# amplifier_v0001_-_1_Channel_Test.net
KiCad netlist of a schematic drawn in EAGLE
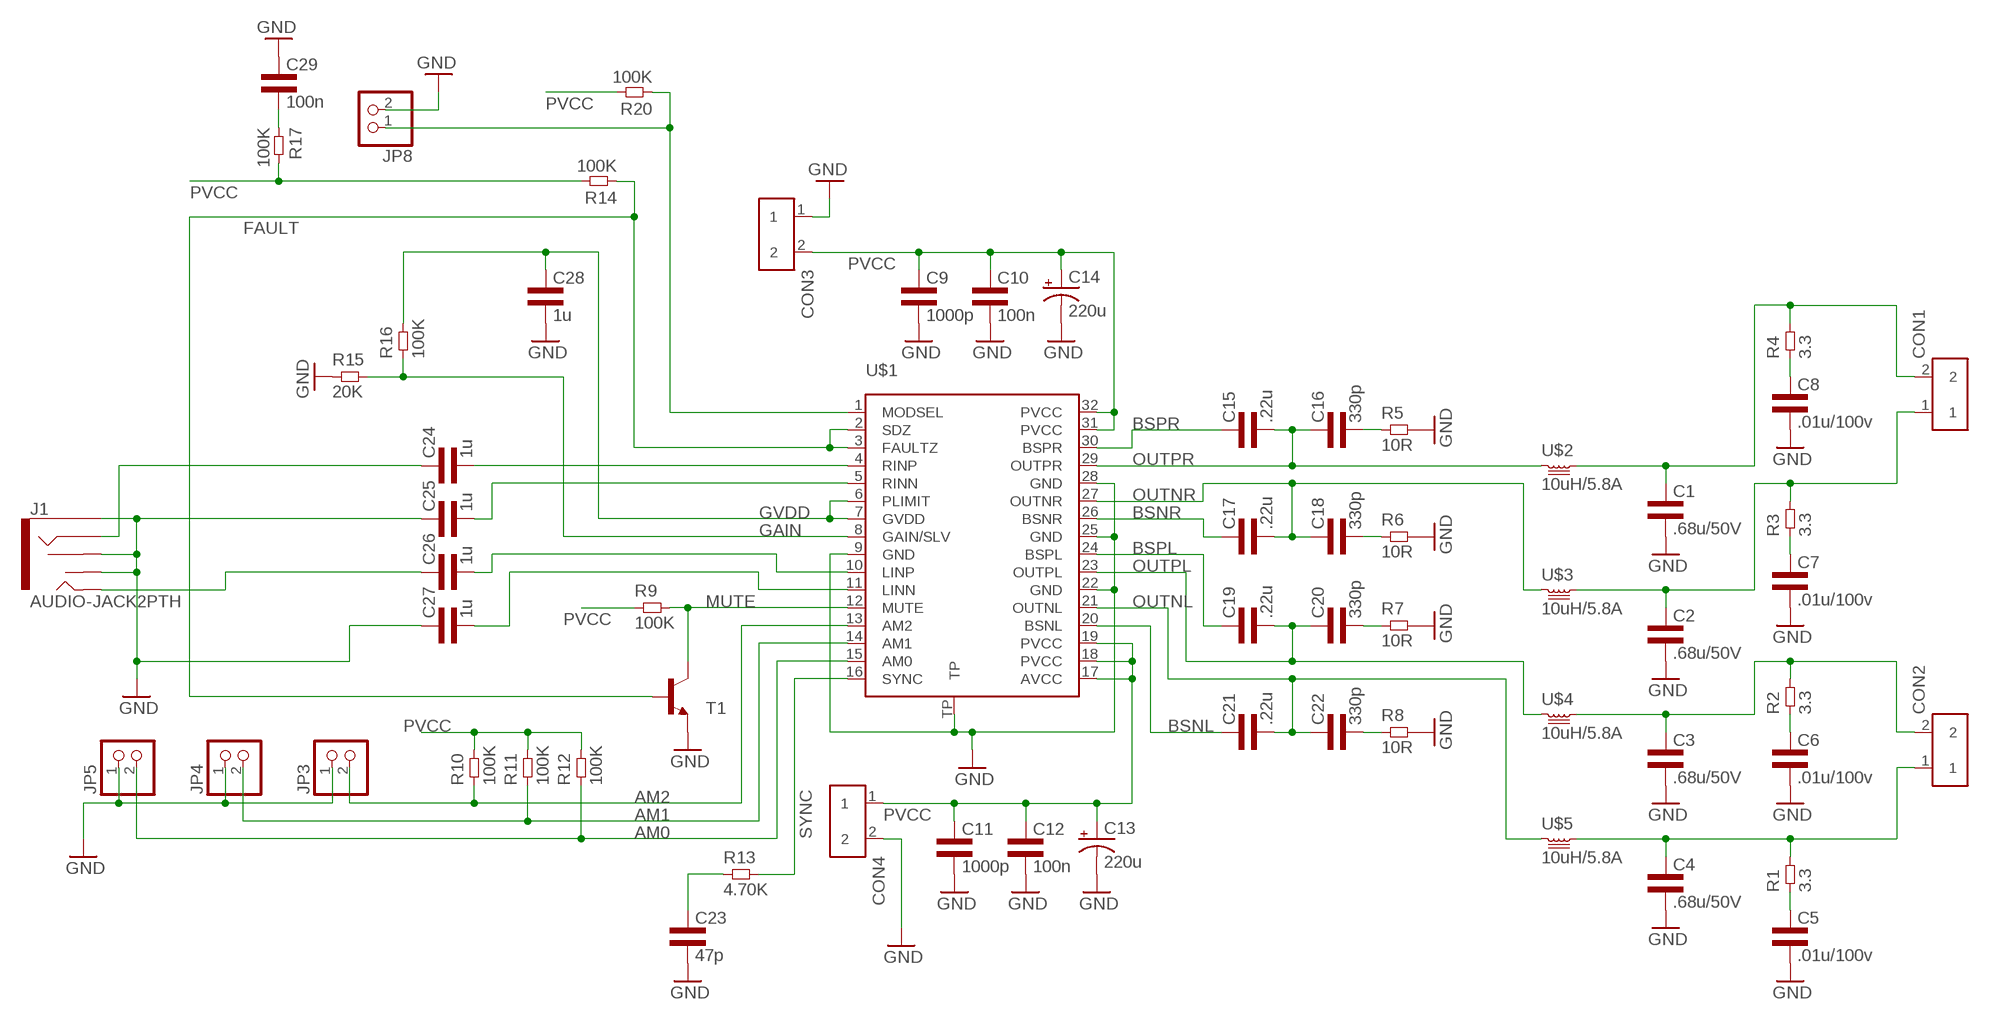
[diagram p0: schematic, sheet 1]

(export (version "E")
  (design (tool "Eeschema 10.0.6"))
  (components
    (comp (ref "C1")
      (value ".68u/50V")
      (footprint "eagle-import:1206L3")
      (libsource (lib "eagle-import") (part "CAP1206L3"))
    )
    (comp (ref "C2")
      (value ".68u/50V")
      (footprint "eagle-import:1206L3")
      (libsource (lib "eagle-import") (part "CAP1206L3"))
    )
    (comp (ref "C3")
      (value ".68u/50V")
      (footprint "eagle-import:1206L3")
      (libsource (lib "eagle-import") (part "CAP1206L3"))
    )
    (comp (ref "C4")
      (value ".68u/50V")
      (footprint "eagle-import:1206L3")
      (libsource (lib "eagle-import") (part "CAP1206L3"))
    )
    (comp (ref "C5")
      (value ".01u/100v")
      (footprint "eagle-import:0805L3")
      (libsource (lib "eagle-import") (part "CAP0805L3"))
    )
    (comp (ref "C6")
      (value ".01u/100v")
      (footprint "eagle-import:0805L3")
      (libsource (lib "eagle-import") (part "CAP0805L3"))
    )
    (comp (ref "C7")
      (value ".01u/100v")
      (footprint "eagle-import:0805L3")
      (libsource (lib "eagle-import") (part "CAP0805L3"))
    )
    (comp (ref "C8")
      (value ".01u/100v")
      (footprint "eagle-import:0805L3")
      (libsource (lib "eagle-import") (part "CAP0805L3"))
    )
    (comp (ref "C9")
      (value "1000p")
      (footprint "eagle-import:0603L3")
      (libsource (lib "eagle-import") (part "CAP0603L3"))
    )
    (comp (ref "C10")
      (value "100n")
      (footprint "eagle-import:0603L3")
      (libsource (lib "eagle-import") (part "CAP0603L3"))
    )
    (comp (ref "C11")
      (value "1000p")
      (footprint "eagle-import:0603L3")
      (libsource (lib "eagle-import") (part "CAP0603L3"))
    )
    (comp (ref "C12")
      (value "100n")
      (footprint "eagle-import:0603L3")
      (libsource (lib "eagle-import") (part "CAP0603L3"))
    )
    (comp (ref "C13")
      (value "220u")
      (footprint "eagle-import:E5-10,5")
      (libsource (lib "eagle-import") (part "CPOL-USE5-10.5"))
    )
    (comp (ref "C14")
      (value "220u")
      (footprint "eagle-import:E5-10,5")
      (libsource (lib "eagle-import") (part "CPOL-USE5-10.5"))
    )
    (comp (ref "C15")
      (value ".22u")
      (footprint "eagle-import:0603L3")
      (libsource (lib "eagle-import") (part "CAP0603L3"))
    )
    (comp (ref "C16")
      (value "330p")
      (footprint "eagle-import:0603L3")
      (libsource (lib "eagle-import") (part "CAP0603L3"))
    )
    (comp (ref "C17")
      (value ".22u")
      (footprint "eagle-import:0603L3")
      (libsource (lib "eagle-import") (part "CAP0603L3"))
    )
    (comp (ref "C18")
      (value "330p")
      (footprint "eagle-import:0603L3")
      (libsource (lib "eagle-import") (part "CAP0603L3"))
    )
    (comp (ref "C19")
      (value ".22u")
      (footprint "eagle-import:0603L3")
      (libsource (lib "eagle-import") (part "CAP0603L3"))
    )
    (comp (ref "C20")
      (value "330p")
      (footprint "eagle-import:0603L3")
      (libsource (lib "eagle-import") (part "CAP0603L3"))
    )
    (comp (ref "C21")
      (value ".22u")
      (footprint "eagle-import:0603L3")
      (libsource (lib "eagle-import") (part "CAP0603L3"))
    )
    (comp (ref "C22")
      (value "330p")
      (footprint "eagle-import:0603L3")
      (libsource (lib "eagle-import") (part "CAP0603L3"))
    )
    (comp (ref "C23")
      (value "47p")
      (footprint "eagle-import:0603L3")
      (libsource (lib "eagle-import") (part "CAP0603L3"))
    )
    (comp (ref "C24")
      (value "1u")
      (footprint "eagle-import:0603L3")
      (libsource (lib "eagle-import") (part "CAP0603L3"))
    )
    (comp (ref "C25")
      (value "1u")
      (footprint "eagle-import:0603L3")
      (libsource (lib "eagle-import") (part "CAP0603L3"))
    )
    (comp (ref "C26")
      (value "1u")
      (footprint "eagle-import:0603L3")
      (libsource (lib "eagle-import") (part "CAP0603L3"))
    )
    (comp (ref "C27")
      (value "1u")
      (footprint "eagle-import:0603L3")
      (libsource (lib "eagle-import") (part "CAP0603L3"))
    )
    (comp (ref "C28")
      (value "1u")
      (footprint "eagle-import:0603L3")
      (libsource (lib "eagle-import") (part "CAP0603L3"))
    )
    (comp (ref "C29")
      (value "100n")
      (footprint "eagle-import:0603L3")
      (libsource (lib "eagle-import") (part "CAP0603L3"))
    )
    (comp (ref "CON1")
      (value "TERM_BLOCK_2")
      (footprint "eagle-import:TERM_BLOCK_2")
      (libsource (lib "eagle-import") (part "TERM_BLOCK_2"))
    )
    (comp (ref "CON2")
      (value "TERM_BLOCK_2")
      (footprint "eagle-import:TERM_BLOCK_2")
      (libsource (lib "eagle-import") (part "TERM_BLOCK_2"))
    )
    (comp (ref "CON3")
      (value "TERM_BLOCK_2")
      (footprint "eagle-import:TERM_BLOCK_2")
      (libsource (lib "eagle-import") (part "TERM_BLOCK_2"))
    )
    (comp (ref "CON4")
      (value "TERM_BLOCK_2")
      (footprint "eagle-import:TERM_BLOCK_2")
      (libsource (lib "eagle-import") (part "TERM_BLOCK_2"))
    )
    (comp (ref "J1")
      (value "AUDIO-JACK2PTH")
      (footprint "eagle-import:AUDIO-JACK")
      (libsource (lib "eagle-import") (part "AUDIO-JACK2PTH"))
    )
    (comp (ref "JP3")
      (value "PINHD-1X2")
      (footprint "eagle-import:1X02")
      (libsource (lib "eagle-import") (part "PINHD-1X2"))
    )
    (comp (ref "JP4")
      (value "PINHD-1X2")
      (footprint "eagle-import:1X02")
      (libsource (lib "eagle-import") (part "PINHD-1X2"))
    )
    (comp (ref "JP5")
      (value "PINHD-1X2")
      (footprint "eagle-import:1X02")
      (libsource (lib "eagle-import") (part "PINHD-1X2"))
    )
    (comp (ref "JP8")
      (value "PINHD-1X2")
      (footprint "eagle-import:1X02")
      (libsource (lib "eagle-import") (part "PINHD-1X2"))
    )
    (comp (ref "R1")
      (value "3.3")
      (footprint "eagle-import:0603L3")
      (libsource (lib "eagle-import") (part "RES0603L3"))
    )
    (comp (ref "R2")
      (value "3.3")
      (footprint "eagle-import:0603L3")
      (libsource (lib "eagle-import") (part "RES0603L3"))
    )
    (comp (ref "R3")
      (value "3.3")
      (footprint "eagle-import:0603L3")
      (libsource (lib "eagle-import") (part "RES0603L3"))
    )
    (comp (ref "R4")
      (value "3.3")
      (footprint "eagle-import:0603L3")
      (libsource (lib "eagle-import") (part "RES0603L3"))
    )
    (comp (ref "R5")
      (value "10R")
      (footprint "eagle-import:0805L3")
      (libsource (lib "eagle-import") (part "RES0805L3"))
    )
    (comp (ref "R6")
      (value "10R")
      (footprint "eagle-import:0805L3")
      (libsource (lib "eagle-import") (part "RES0805L3"))
    )
    (comp (ref "R7")
      (value "10R")
      (footprint "eagle-import:0805L3")
      (libsource (lib "eagle-import") (part "RES0805L3"))
    )
    (comp (ref "R8")
      (value "10R")
      (footprint "eagle-import:0805L3")
      (libsource (lib "eagle-import") (part "RES0805L3"))
    )
    (comp (ref "R9")
      (value "100K")
      (footprint "eagle-import:0603L3")
      (libsource (lib "eagle-import") (part "RES0603L3"))
    )
    (comp (ref "R10")
      (value "100K")
      (footprint "eagle-import:0603L3")
      (libsource (lib "eagle-import") (part "RES0603L3"))
    )
    (comp (ref "R11")
      (value "100K")
      (footprint "eagle-import:0603L3")
      (libsource (lib "eagle-import") (part "RES0603L3"))
    )
    (comp (ref "R12")
      (value "100K")
      (footprint "eagle-import:0603L3")
      (libsource (lib "eagle-import") (part "RES0603L3"))
    )
    (comp (ref "R13")
      (value "4.70K")
      (footprint "eagle-import:0603L3")
      (libsource (lib "eagle-import") (part "RES0603L3"))
    )
    (comp (ref "R14")
      (value "100K")
      (footprint "eagle-import:0603L3")
      (libsource (lib "eagle-import") (part "RES0603L3"))
    )
    (comp (ref "R15")
      (value "20K")
      (footprint "eagle-import:0603L3")
      (libsource (lib "eagle-import") (part "RES0603L3"))
    )
    (comp (ref "R16")
      (value "100K")
      (footprint "eagle-import:0603L3")
      (libsource (lib "eagle-import") (part "RES0603L3"))
    )
    (comp (ref "R17")
      (value "100K")
      (footprint "eagle-import:0603L3")
      (libsource (lib "eagle-import") (part "RES0603L3"))
    )
    (comp (ref "R20")
      (value "100K")
      (footprint "eagle-import:0603L3")
      (libsource (lib "eagle-import") (part "RES0603L3"))
    )
    (comp (ref "T1")
      (value "TRANSISTOR_MMBT2222ALT1-NPN-SOT23-BEC")
      (footprint "eagle-import:TRANSISTOR_SOT23-BEC")
      (libsource (lib "eagle-import") (part "TRANSISTOR_-NPN-SOT23-BECMMBT2222ALT1"))
    )
    (comp (ref "U$1")
      (value "TPA3116")
      (footprint "eagle-import:R-PDSO-32")
      (libsource (lib "eagle-import") (part "TPA3116"))
    )
    (comp (ref "U$2")
      (value "10uH/5.8A")
      (footprint "eagle-import:DR127")
      (libsource (lib "eagle-import") (part "INDUCTORDR127"))
    )
    (comp (ref "U$3")
      (value "10uH/5.8A")
      (footprint "eagle-import:DR127")
      (libsource (lib "eagle-import") (part "INDUCTORDR127"))
    )
    (comp (ref "U$4")
      (value "10uH/5.8A")
      (footprint "eagle-import:DR127")
      (libsource (lib "eagle-import") (part "INDUCTORDR127"))
    )
    (comp (ref "U$5")
      (value "10uH/5.8A")
      (footprint "eagle-import:DR127")
      (libsource (lib "eagle-import") (part "INDUCTORDR127"))
    )
  )
  (nets
    (net (code "1") (name "/AM0") (class "Default")
      (node (ref "JP5") (pin "2") (pinfunction "2_2") (pintype "passive"))
      (node (ref "R12") (pin "P$1") (pinfunction "1_P$1") (pintype "bidirectional"))
      (node (ref "U$1") (pin "15") (pinfunction "AM0_15") (pintype "bidirectional"))
    )
    (net (code "2") (name "/AM1") (class "Default")
      (node (ref "JP4") (pin "2") (pinfunction "2_2") (pintype "passive"))
      (node (ref "R11") (pin "P$1") (pinfunction "1_P$1") (pintype "bidirectional"))
      (node (ref "U$1") (pin "14") (pinfunction "AM1_14") (pintype "bidirectional"))
    )
    (net (code "3") (name "/AM2") (class "Default")
      (node (ref "JP3") (pin "2") (pinfunction "2_2") (pintype "passive"))
      (node (ref "R10") (pin "P$1") (pinfunction "1_P$1") (pintype "bidirectional"))
      (node (ref "U$1") (pin "13") (pinfunction "AM2_13") (pintype "bidirectional"))
    )
    (net (code "4") (name "/BSNL") (class "Default")
      (node (ref "C21") (pin "P$1") (pinfunction "1_P$1") (pintype "bidirectional"))
      (node (ref "U$1") (pin "20") (pinfunction "BSNL_20") (pintype "bidirectional"))
    )
    (net (code "5") (name "/BSNR") (class "Default")
      (node (ref "C17") (pin "P$1") (pinfunction "1_P$1") (pintype "bidirectional"))
      (node (ref "U$1") (pin "26") (pinfunction "BSNR_26") (pintype "bidirectional"))
    )
    (net (code "6") (name "/BSPL") (class "Default")
      (node (ref "C19") (pin "P$1") (pinfunction "1_P$1") (pintype "bidirectional"))
      (node (ref "U$1") (pin "24") (pinfunction "BSPL_24") (pintype "bidirectional"))
    )
    (net (code "7") (name "/BSPR") (class "Default")
      (node (ref "C15") (pin "P$1") (pinfunction "1_P$1") (pintype "bidirectional"))
      (node (ref "U$1") (pin "30") (pinfunction "BSPR_30") (pintype "bidirectional"))
    )
    (net (code "8") (name "/FAULT") (class "Default")
      (node (ref "R14") (pin "P$1") (pinfunction "1_P$1") (pintype "bidirectional"))
      (node (ref "T1") (pin "B") (pinfunction "B_B") (pintype "passive"))
      (node (ref "U$1") (pin "2") (pinfunction "SDZ_2") (pintype "bidirectional"))
      (node (ref "U$1") (pin "3") (pinfunction "FAULTZ_3") (pintype "bidirectional"))
    )
    (net (code "9") (name "/GAIN") (class "Default")
      (node (ref "R15") (pin "P$2") (pinfunction "2_P$2") (pintype "bidirectional"))
      (node (ref "R16") (pin "P$1") (pinfunction "1_P$1") (pintype "bidirectional"))
      (node (ref "U$1") (pin "8") (pinfunction "GAIN/SLV_8") (pintype "bidirectional"))
    )
    (net (code "10") (name "/GVDD") (class "Default")
      (node (ref "C28") (pin "P$1") (pinfunction "1_P$1") (pintype "bidirectional"))
      (node (ref "R16") (pin "P$2") (pinfunction "2_P$2") (pintype "bidirectional"))
      (node (ref "U$1") (pin "6") (pinfunction "PLIMIT_6") (pintype "bidirectional"))
      (node (ref "U$1") (pin "7") (pinfunction "GVDD_7") (pintype "bidirectional"))
    )
    (net (code "11") (name "/MUTE") (class "Default")
      (node (ref "R9") (pin "P$2") (pinfunction "2_P$2") (pintype "bidirectional"))
      (node (ref "T1") (pin "C") (pinfunction "C_C") (pintype "passive"))
      (node (ref "U$1") (pin "12") (pinfunction "MUTE_12") (pintype "bidirectional"))
    )
    (net (code "12") (name "/OUTNL") (class "Default")
      (node (ref "C21") (pin "P$2") (pinfunction "2_P$2") (pintype "bidirectional"))
      (node (ref "C22") (pin "P$1") (pinfunction "1_P$1") (pintype "bidirectional"))
      (node (ref "U$1") (pin "21") (pinfunction "OUTNL_21") (pintype "bidirectional"))
      (node (ref "U$5") (pin "1") (pinfunction "1_1") (pintype "bidirectional"))
    )
    (net (code "13") (name "/OUTNR") (class "Default")
      (node (ref "C17") (pin "P$2") (pinfunction "2_P$2") (pintype "bidirectional"))
      (node (ref "C18") (pin "P$1") (pinfunction "1_P$1") (pintype "bidirectional"))
      (node (ref "U$1") (pin "27") (pinfunction "OUTNR_27") (pintype "bidirectional"))
      (node (ref "U$3") (pin "1") (pinfunction "1_1") (pintype "bidirectional"))
    )
    (net (code "14") (name "/OUTPL") (class "Default")
      (node (ref "C19") (pin "P$2") (pinfunction "2_P$2") (pintype "bidirectional"))
      (node (ref "C20") (pin "P$1") (pinfunction "1_P$1") (pintype "bidirectional"))
      (node (ref "U$1") (pin "23") (pinfunction "OUTPL_23") (pintype "bidirectional"))
      (node (ref "U$4") (pin "1") (pinfunction "1_1") (pintype "bidirectional"))
    )
    (net (code "15") (name "/OUTPR") (class "Default")
      (node (ref "C15") (pin "P$2") (pinfunction "2_P$2") (pintype "bidirectional"))
      (node (ref "C16") (pin "P$1") (pinfunction "1_P$1") (pintype "bidirectional"))
      (node (ref "U$1") (pin "29") (pinfunction "OUTPR_29") (pintype "bidirectional"))
      (node (ref "U$2") (pin "1") (pinfunction "1_1") (pintype "bidirectional"))
    )
    (net (code "16") (name "/PVCC") (class "Default")
      (node (ref "C10") (pin "P$1") (pinfunction "1_P$1") (pintype "bidirectional"))
      (node (ref "C11") (pin "P$1") (pinfunction "1_P$1") (pintype "bidirectional"))
      (node (ref "C12") (pin "P$1") (pinfunction "1_P$1") (pintype "bidirectional"))
      (node (ref "C13") (pin "+") (pinfunction "+_+") (pintype "passive"))
      (node (ref "C14") (pin "+") (pinfunction "+_+") (pintype "passive"))
      (node (ref "C9") (pin "P$1") (pinfunction "1_P$1") (pintype "bidirectional"))
      (node (ref "CON3") (pin "2") (pinfunction "2_2") (pintype "bidirectional"))
      (node (ref "CON4") (pin "1") (pinfunction "1_1") (pintype "bidirectional"))
      (node (ref "R10") (pin "P$2") (pinfunction "2_P$2") (pintype "bidirectional"))
      (node (ref "R11") (pin "P$2") (pinfunction "2_P$2") (pintype "bidirectional"))
      (node (ref "R12") (pin "P$2") (pinfunction "2_P$2") (pintype "bidirectional"))
      (node (ref "R14") (pin "P$2") (pinfunction "2_P$2") (pintype "bidirectional"))
      (node (ref "R17") (pin "P$2") (pinfunction "2_P$2") (pintype "bidirectional"))
      (node (ref "R20") (pin "P$2") (pinfunction "2_P$2") (pintype "bidirectional"))
      (node (ref "R9") (pin "P$1") (pinfunction "1_P$1") (pintype "bidirectional"))
      (node (ref "U$1") (pin "17") (pinfunction "AVCC_17") (pintype "bidirectional"))
      (node (ref "U$1") (pin "18") (pinfunction "PVCC_18") (pintype "bidirectional"))
      (node (ref "U$1") (pin "19") (pinfunction "PVCC_19") (pintype "bidirectional"))
      (node (ref "U$1") (pin "31") (pinfunction "PVCC_31") (pintype "bidirectional"))
      (node (ref "U$1") (pin "32") (pinfunction "PVCC_32") (pintype "bidirectional"))
    )
    (net (code "17") (name "/SYNC") (class "Default")
      (node (ref "R13") (pin "P$2") (pinfunction "2_P$2") (pintype "bidirectional"))
      (node (ref "U$1") (pin "16") (pinfunction "SYNC_16") (pintype "bidirectional"))
    )
    (net (code "18") (name "GND") (class "Default")
      (node (ref "C1") (pin "2") (pinfunction "2_2") (pintype "bidirectional"))
      (node (ref "C10") (pin "P$2") (pinfunction "2_P$2") (pintype "bidirectional"))
      (node (ref "C11") (pin "P$2") (pinfunction "2_P$2") (pintype "bidirectional"))
      (node (ref "C12") (pin "P$2") (pinfunction "2_P$2") (pintype "bidirectional"))
      (node (ref "C13") (pin "-") (pinfunction "-_-") (pintype "passive"))
      (node (ref "C14") (pin "-") (pinfunction "-_-") (pintype "passive"))
      (node (ref "C2") (pin "2") (pinfunction "2_2") (pintype "bidirectional"))
      (node (ref "C23") (pin "P$2") (pinfunction "2_P$2") (pintype "bidirectional"))
      (node (ref "C25") (pin "P$1") (pinfunction "1_P$1") (pintype "bidirectional"))
      (node (ref "C27") (pin "P$1") (pinfunction "1_P$1") (pintype "bidirectional"))
      (node (ref "C28") (pin "P$2") (pinfunction "2_P$2") (pintype "bidirectional"))
      (node (ref "C29") (pin "P$1") (pinfunction "1_P$1") (pintype "bidirectional"))
      (node (ref "C3") (pin "2") (pinfunction "2_2") (pintype "bidirectional"))
      (node (ref "C4") (pin "2") (pinfunction "2_2") (pintype "bidirectional"))
      (node (ref "C5") (pin "2") (pinfunction "2_2") (pintype "bidirectional"))
      (node (ref "C6") (pin "2") (pinfunction "2_2") (pintype "bidirectional"))
      (node (ref "C7") (pin "2") (pinfunction "2_2") (pintype "bidirectional"))
      (node (ref "C8") (pin "2") (pinfunction "2_2") (pintype "bidirectional"))
      (node (ref "C9") (pin "P$2") (pinfunction "2_P$2") (pintype "bidirectional"))
      (node (ref "CON3") (pin "1") (pinfunction "1_1") (pintype "bidirectional"))
      (node (ref "CON4") (pin "2") (pinfunction "2_2") (pintype "bidirectional"))
      (node (ref "J1") (pin "RSH") (pinfunction "RSH_RSH") (pintype "bidirectional"))
      (node (ref "J1") (pin "SLEEVE") (pinfunction "SLEEVE_SLEEVE") (pintype "bidirectional"))
      (node (ref "J1") (pin "TSH") (pinfunction "TSH_TSH") (pintype "bidirectional"))
      (node (ref "JP3") (pin "1") (pinfunction "1_1") (pintype "passive"))
      (node (ref "JP4") (pin "1") (pinfunction "1_1") (pintype "passive"))
      (node (ref "JP5") (pin "1") (pinfunction "1_1") (pintype "passive"))
      (node (ref "JP8") (pin "2") (pinfunction "2_2") (pintype "passive"))
      (node (ref "R15") (pin "P$1") (pinfunction "1_P$1") (pintype "bidirectional"))
      (node (ref "R5") (pin "2") (pinfunction "2_2") (pintype "bidirectional"))
      (node (ref "R6") (pin "2") (pinfunction "2_2") (pintype "bidirectional"))
      (node (ref "R7") (pin "2") (pinfunction "2_2") (pintype "bidirectional"))
      (node (ref "R8") (pin "2") (pinfunction "2_2") (pintype "bidirectional"))
      (node (ref "T1") (pin "E") (pinfunction "E_E") (pintype "passive"))
      (node (ref "U$1") (pin "22") (pinfunction "GND_22") (pintype "bidirectional"))
      (node (ref "U$1") (pin "25") (pinfunction "GND_25") (pintype "bidirectional"))
      (node (ref "U$1") (pin "28") (pinfunction "GND_28") (pintype "bidirectional"))
      (node (ref "U$1") (pin "9") (pinfunction "GND_9") (pintype "bidirectional"))
      (node (ref "U$1") (pin "TP") (pinfunction "TP_TP") (pintype "bidirectional"))
    )
    (net (code "19") (name "Net-(C16-2)") (class "Default")
      (node (ref "C16") (pin "P$2") (pinfunction "2_P$2") (pintype "bidirectional"))
      (node (ref "R5") (pin "1") (pinfunction "1_1") (pintype "bidirectional"))
    )
    (net (code "20") (name "Net-(C18-2)") (class "Default")
      (node (ref "C18") (pin "P$2") (pinfunction "2_P$2") (pintype "bidirectional"))
      (node (ref "R6") (pin "1") (pinfunction "1_1") (pintype "bidirectional"))
    )
    (net (code "21") (name "Net-(C20-2)") (class "Default")
      (node (ref "C20") (pin "P$2") (pinfunction "2_P$2") (pintype "bidirectional"))
      (node (ref "R7") (pin "1") (pinfunction "1_1") (pintype "bidirectional"))
    )
    (net (code "22") (name "Net-(C22-2)") (class "Default")
      (node (ref "C22") (pin "P$2") (pinfunction "2_P$2") (pintype "bidirectional"))
      (node (ref "R8") (pin "1") (pinfunction "1_1") (pintype "bidirectional"))
    )
    (net (code "23") (name "Net-(C23-1)") (class "Default")
      (node (ref "C23") (pin "P$1") (pinfunction "1_P$1") (pintype "bidirectional"))
      (node (ref "R13") (pin "P$1") (pinfunction "1_P$1") (pintype "bidirectional"))
    )
    (net (code "24") (name "Net-(C24-1)") (class "Default")
      (node (ref "C24") (pin "P$1") (pinfunction "1_P$1") (pintype "bidirectional"))
      (node (ref "J1") (pin "RING") (pinfunction "RING_RING") (pintype "bidirectional"))
    )
    (net (code "25") (name "Net-(C24-2)") (class "Default")
      (node (ref "C24") (pin "P$2") (pinfunction "2_P$2") (pintype "bidirectional"))
      (node (ref "U$1") (pin "4") (pinfunction "RINP_4") (pintype "bidirectional"))
    )
    (net (code "26") (name "Net-(C25-2)") (class "Default")
      (node (ref "C25") (pin "P$2") (pinfunction "2_P$2") (pintype "bidirectional"))
      (node (ref "U$1") (pin "5") (pinfunction "RINN_5") (pintype "bidirectional"))
    )
    (net (code "27") (name "Net-(C26-1)") (class "Default")
      (node (ref "C26") (pin "P$1") (pinfunction "1_P$1") (pintype "bidirectional"))
      (node (ref "J1") (pin "TIP") (pinfunction "TIP_TIP") (pintype "bidirectional"))
    )
    (net (code "28") (name "Net-(C26-2)") (class "Default")
      (node (ref "C26") (pin "P$2") (pinfunction "2_P$2") (pintype "bidirectional"))
      (node (ref "U$1") (pin "10") (pinfunction "LINP_10") (pintype "bidirectional"))
    )
    (net (code "29") (name "Net-(C27-2)") (class "Default")
      (node (ref "C27") (pin "P$2") (pinfunction "2_P$2") (pintype "bidirectional"))
      (node (ref "U$1") (pin "11") (pinfunction "LINN_11") (pintype "bidirectional"))
    )
    (net (code "30") (name "Net-(C29-2)") (class "Default")
      (node (ref "C29") (pin "P$2") (pinfunction "2_P$2") (pintype "bidirectional"))
      (node (ref "R17") (pin "P$1") (pinfunction "1_P$1") (pintype "bidirectional"))
    )
    (net (code "31") (name "Net-(R1-1)") (class "Default")
      (node (ref "C5") (pin "1") (pinfunction "1_1") (pintype "bidirectional"))
      (node (ref "R1") (pin "P$1") (pinfunction "1_P$1") (pintype "bidirectional"))
    )
    (net (code "32") (name "Net-(R1-2)") (class "Default")
      (node (ref "C4") (pin "1") (pinfunction "1_1") (pintype "bidirectional"))
      (node (ref "CON2") (pin "1") (pinfunction "1_1") (pintype "bidirectional"))
      (node (ref "R1") (pin "P$2") (pinfunction "2_P$2") (pintype "bidirectional"))
      (node (ref "U$5") (pin "2") (pinfunction "2_2") (pintype "bidirectional"))
    )
    (net (code "33") (name "Net-(R2-1)") (class "Default")
      (node (ref "C6") (pin "1") (pinfunction "1_1") (pintype "bidirectional"))
      (node (ref "R2") (pin "P$1") (pinfunction "1_P$1") (pintype "bidirectional"))
    )
    (net (code "34") (name "Net-(R2-2)") (class "Default")
      (node (ref "C3") (pin "1") (pinfunction "1_1") (pintype "bidirectional"))
      (node (ref "CON2") (pin "2") (pinfunction "2_2") (pintype "bidirectional"))
      (node (ref "R2") (pin "P$2") (pinfunction "2_P$2") (pintype "bidirectional"))
      (node (ref "U$4") (pin "2") (pinfunction "2_2") (pintype "bidirectional"))
    )
    (net (code "35") (name "Net-(R3-1)") (class "Default")
      (node (ref "C7") (pin "1") (pinfunction "1_1") (pintype "bidirectional"))
      (node (ref "R3") (pin "P$1") (pinfunction "1_P$1") (pintype "bidirectional"))
    )
    (net (code "36") (name "Net-(R3-2)") (class "Default")
      (node (ref "C2") (pin "1") (pinfunction "1_1") (pintype "bidirectional"))
      (node (ref "CON1") (pin "1") (pinfunction "1_1") (pintype "bidirectional"))
      (node (ref "R3") (pin "P$2") (pinfunction "2_P$2") (pintype "bidirectional"))
      (node (ref "U$3") (pin "2") (pinfunction "2_2") (pintype "bidirectional"))
    )
    (net (code "37") (name "Net-(R4-1)") (class "Default")
      (node (ref "C8") (pin "1") (pinfunction "1_1") (pintype "bidirectional"))
      (node (ref "R4") (pin "P$1") (pinfunction "1_P$1") (pintype "bidirectional"))
    )
    (net (code "38") (name "Net-(R4-2)") (class "Default")
      (node (ref "C1") (pin "1") (pinfunction "1_1") (pintype "bidirectional"))
      (node (ref "CON1") (pin "2") (pinfunction "2_2") (pintype "bidirectional"))
      (node (ref "R4") (pin "P$2") (pinfunction "2_P$2") (pintype "bidirectional"))
      (node (ref "U$2") (pin "2") (pinfunction "2_2") (pintype "bidirectional"))
    )
    (net (code "39") (name "Net-(R20-1)") (class "Default")
      (node (ref "JP8") (pin "1") (pinfunction "1_1") (pintype "passive"))
      (node (ref "R20") (pin "P$1") (pinfunction "1_P$1") (pintype "bidirectional"))
      (node (ref "U$1") (pin "1") (pinfunction "MODSEL_1") (pintype "bidirectional"))
    )
  )
)
